# FOTA_Status_LED.net
KiCad netlist of a schematic drawn in Altium Designer
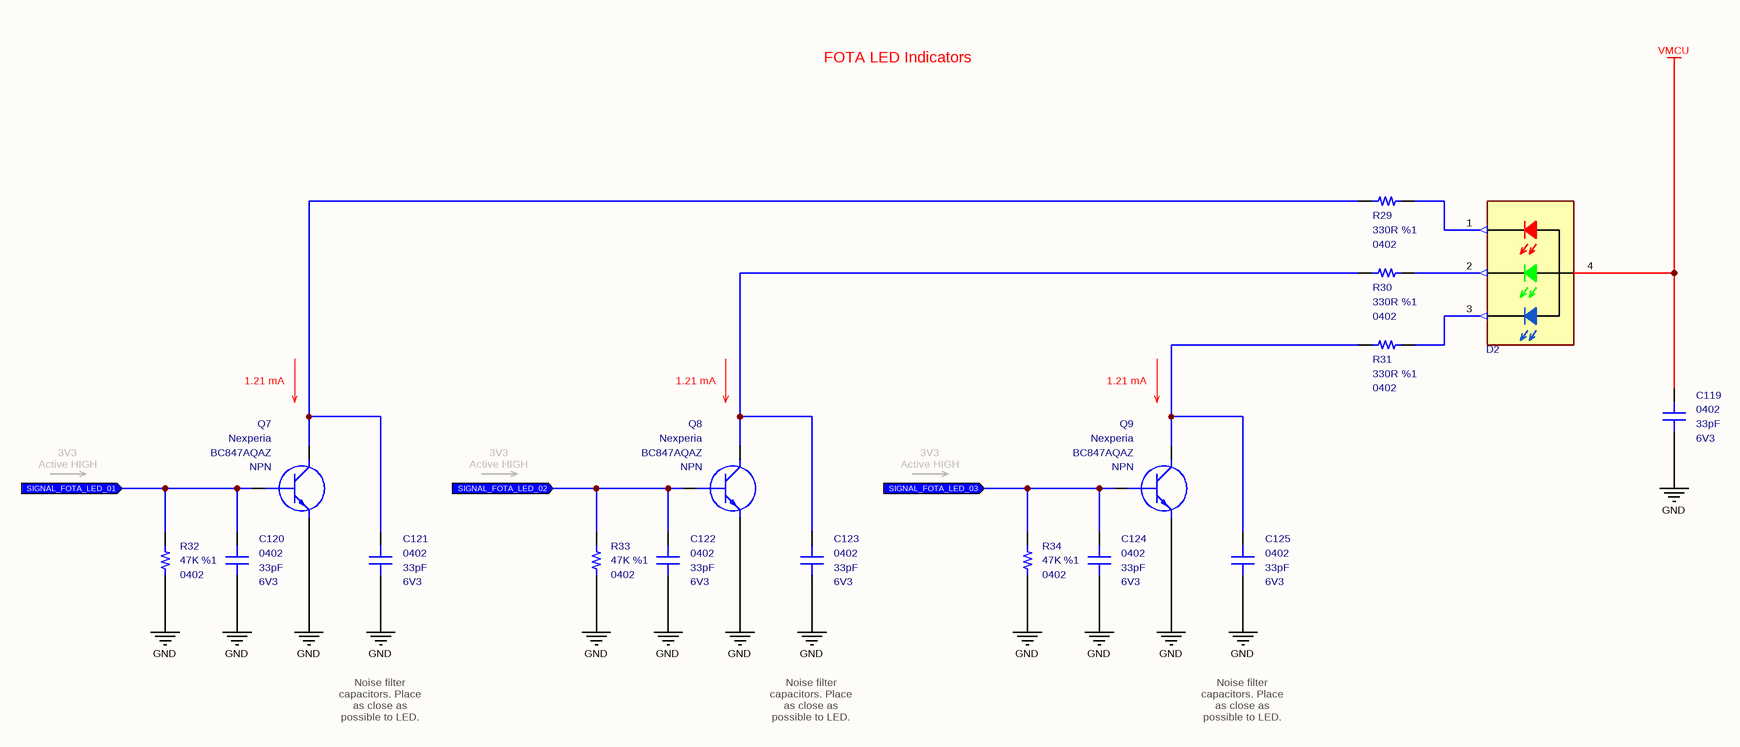
[diagram p0: FOTA Status LED.SchDoc]

(export (version "E")
  (design (tool "Eeschema 10.0.6"))
  (components
    (comp (ref "C119")
      (value "33pF")
      (footprint "CAPACITOR_0402")
      (description "Capacitor - 33pF [0402] (Ceramic)")
      (fields
        (field (name "MANUFACTURER_PART_NUMBER") "C0402C330J9RACAUTO")
        (field (name "MOUSER_PART_NUMBER") "80-C0402C330J9RAUTO")
        (field (name "CASE") "0402")
        (field (name "VOLTAGE") "6V3")
      )
      (libsource (lib "Ovoo_Schematic") (part "Capacitor - 33pF [0402-6V3]"))
    )
    (comp (ref "C120")
      (value "33pF")
      (footprint "CAPACITOR_0402")
      (description "Capacitor - 33pF [0402] (Ceramic)")
      (fields
        (field (name "MANUFACTURER_PART_NUMBER") "C0402C330J9RACAUTO")
        (field (name "MOUSER_PART_NUMBER") "80-C0402C330J9RAUTO")
        (field (name "CASE") "0402")
        (field (name "VOLTAGE") "6V3")
      )
      (libsource (lib "Ovoo_Schematic") (part "Capacitor - 33pF [0402-6V3]"))
    )
    (comp (ref "C121")
      (value "33pF")
      (footprint "CAPACITOR_0402")
      (description "Capacitor - 33pF [0402] (Ceramic)")
      (fields
        (field (name "MANUFACTURER_PART_NUMBER") "C0402C330J9RACAUTO")
        (field (name "MOUSER_PART_NUMBER") "80-C0402C330J9RAUTO")
        (field (name "CASE") "0402")
        (field (name "VOLTAGE") "6V3")
      )
      (libsource (lib "Ovoo_Schematic") (part "Capacitor - 33pF [0402-6V3]"))
    )
    (comp (ref "C122")
      (value "33pF")
      (footprint "CAPACITOR_0402")
      (description "Capacitor - 33pF [0402] (Ceramic)")
      (fields
        (field (name "MANUFACTURER_PART_NUMBER") "C0402C330J9RACAUTO")
        (field (name "MOUSER_PART_NUMBER") "80-C0402C330J9RAUTO")
        (field (name "CASE") "0402")
        (field (name "VOLTAGE") "6V3")
      )
      (libsource (lib "Ovoo_Schematic") (part "Capacitor - 33pF [0402-6V3]"))
    )
    (comp (ref "C123")
      (value "33pF")
      (footprint "CAPACITOR_0402")
      (description "Capacitor - 33pF [0402] (Ceramic)")
      (fields
        (field (name "MANUFACTURER_PART_NUMBER") "C0402C330J9RACAUTO")
        (field (name "MOUSER_PART_NUMBER") "80-C0402C330J9RAUTO")
        (field (name "CASE") "0402")
        (field (name "VOLTAGE") "6V3")
      )
      (libsource (lib "Ovoo_Schematic") (part "Capacitor - 33pF [0402-6V3]"))
    )
    (comp (ref "C124")
      (value "33pF")
      (footprint "CAPACITOR_0402")
      (description "Capacitor - 33pF [0402] (Ceramic)")
      (fields
        (field (name "MANUFACTURER_PART_NUMBER") "C0402C330J9RACAUTO")
        (field (name "MOUSER_PART_NUMBER") "80-C0402C330J9RAUTO")
        (field (name "CASE") "0402")
        (field (name "VOLTAGE") "6V3")
      )
      (libsource (lib "Ovoo_Schematic") (part "Capacitor - 33pF [0402-6V3]"))
    )
    (comp (ref "C125")
      (value "33pF")
      (footprint "CAPACITOR_0402")
      (description "Capacitor - 33pF [0402] (Ceramic)")
      (fields
        (field (name "MANUFACTURER_PART_NUMBER") "C0402C330J9RACAUTO")
        (field (name "MOUSER_PART_NUMBER") "80-C0402C330J9RAUTO")
        (field (name "CASE") "0402")
        (field (name "VOLTAGE") "6V3")
      )
      (libsource (lib "Ovoo_Schematic") (part "Capacitor - 33pF [0402-6V3]"))
    )
    (comp (ref "D2")
      (value "150066M153000")
      (footprint "Wurth_0606")
      (description "Standard LEDs - SMD PICOLED series Red LED")
      (fields (field (name "MOUSER PART NUMBER") "710-150066M153000"))
      (libsource (lib "Ovoo_Library") (part "Diode - RGB LED (150066M153000)"))
    )
    (comp (ref "Q7")
      (value "Bipolar NPN Transistors")
      (footprint "SOT1215")
      (description "Bipolar Transistors - BJT BC847AQA/DFN1010D-3/REEL 7\" Q2")
      (fields
        (field (name "MOUSER_PART_NUMBER") "771-BC847AQAZ")
        (field (name "MANUFACTURER_NAME") "Nexperia")
        (field (name "MANUFACTURER_PART_NUMBER") "BC847AQAZ")
        (field (name "POLARITY") "NPN")
      )
      (libsource (lib "Ovoo_Schematic") (part "Transistor - BC847"))
    )
    (comp (ref "Q8")
      (value "Bipolar NPN Transistors")
      (footprint "SOT1215")
      (description "Bipolar Transistors - BJT BC847AQA/DFN1010D-3/REEL 7\" Q2")
      (fields
        (field (name "MOUSER_PART_NUMBER") "771-BC847AQAZ")
        (field (name "MANUFACTURER_NAME") "Nexperia")
        (field (name "MANUFACTURER_PART_NUMBER") "BC847AQAZ")
        (field (name "POLARITY") "NPN")
      )
      (libsource (lib "Ovoo_Schematic") (part "Transistor - BC847"))
    )
    (comp (ref "Q9")
      (value "Bipolar NPN Transistors")
      (footprint "SOT1215")
      (description "Bipolar Transistors - BJT BC847AQA/DFN1010D-3/REEL 7\" Q2")
      (fields
        (field (name "MOUSER_PART_NUMBER") "771-BC847AQAZ")
        (field (name "MANUFACTURER_NAME") "Nexperia")
        (field (name "MANUFACTURER_PART_NUMBER") "BC847AQAZ")
        (field (name "POLARITY") "NPN")
      )
      (libsource (lib "Ovoo_Schematic") (part "Transistor - BC847"))
    )
    (comp (ref "R29")
      (value "330R")
      (footprint "RESISTOR_0402")
      (description "Thick Film Resistors - SMD 1/16 W 330 Ohm 1%")
      (fields
        (field (name "MANUFACTURER_PART_NUMBER") "CRCW0402330RFKED")
        (field (name "MOUSER_PART_NUMBER") "71-CRCW0402-330-E3")
        (field (name "TOLERANCE") "%1")
        (field (name "CASE") "0402")
      )
      (libsource (lib "Ovoo_Schematic") (part "Resistor - 330R"))
    )
    (comp (ref "R30")
      (value "330R")
      (footprint "RESISTOR_0402")
      (description "Thick Film Resistors - SMD 1/16 W 330 Ohm 1%")
      (fields
        (field (name "MANUFACTURER_PART_NUMBER") "CRCW0402330RFKED")
        (field (name "MOUSER_PART_NUMBER") "71-CRCW0402-330-E3")
        (field (name "TOLERANCE") "%1")
        (field (name "CASE") "0402")
      )
      (libsource (lib "Ovoo_Schematic") (part "Resistor - 330R"))
    )
    (comp (ref "R31")
      (value "330R")
      (footprint "RESISTOR_0402")
      (description "Thick Film Resistors - SMD 1/16 W 330 Ohm 1%")
      (fields
        (field (name "MANUFACTURER_PART_NUMBER") "CRCW0402330RFKED")
        (field (name "MOUSER_PART_NUMBER") "71-CRCW0402-330-E3")
        (field (name "TOLERANCE") "%1")
        (field (name "CASE") "0402")
      )
      (libsource (lib "Ovoo_Schematic") (part "Resistor - 330R"))
    )
    (comp (ref "R32")
      (value "47K")
      (footprint "RESISTOR_0402")
      (description "Thick Film Resistors - SMD 1/16 W 47 Kohms 1%")
      (fields
        (field (name "MANUFACTURER_PART_NUMBER") "CRCW040247K0FKED")
        (field (name "MOUSER_PART_NUMBER") "71-CRCW0402-47K-E3")
        (field (name "TOLERANCE") "%1")
        (field (name "CASE") "0402")
      )
      (libsource (lib "Ovoo_Schematic") (part "Resistor - 47K"))
    )
    (comp (ref "R33")
      (value "47K")
      (footprint "RESISTOR_0402")
      (description "Thick Film Resistors - SMD 1/16 W 47 Kohms 1%")
      (fields
        (field (name "MANUFACTURER_PART_NUMBER") "CRCW040247K0FKED")
        (field (name "MOUSER_PART_NUMBER") "71-CRCW0402-47K-E3")
        (field (name "TOLERANCE") "%1")
        (field (name "CASE") "0402")
      )
      (libsource (lib "Ovoo_Schematic") (part "Resistor - 47K"))
    )
    (comp (ref "R34")
      (value "47K")
      (footprint "RESISTOR_0402")
      (description "Thick Film Resistors - SMD 1/16 W 47 Kohms 1%")
      (fields
        (field (name "MANUFACTURER_PART_NUMBER") "CRCW040247K0FKED")
        (field (name "MOUSER_PART_NUMBER") "71-CRCW0402-47K-E3")
        (field (name "TOLERANCE") "%1")
        (field (name "CASE") "0402")
      )
      (libsource (lib "Ovoo_Schematic") (part "Resistor - 47K"))
    )
  )
  (nets
    (net (code "1") (name "/SIGNAL_FOTA_LED_01") (class "Default")
      (node (ref "C120") (pin "1") (pinfunction "1_1") (pintype "passive"))
      (node (ref "Q7") (pin "1") (pinfunction "B_1") (pintype "passive"))
      (node (ref "R32") (pin "2") (pinfunction "2_2") (pintype "passive"))
    )
    (net (code "2") (name "/SIGNAL_FOTA_LED_02") (class "Default")
      (node (ref "C122") (pin "1") (pinfunction "1_1") (pintype "passive"))
      (node (ref "Q8") (pin "1") (pinfunction "B_1") (pintype "passive"))
      (node (ref "R33") (pin "2") (pinfunction "2_2") (pintype "passive"))
    )
    (net (code "3") (name "/SIGNAL_FOTA_LED_03") (class "Default")
      (node (ref "C124") (pin "1") (pinfunction "1_1") (pintype "passive"))
      (node (ref "Q9") (pin "1") (pinfunction "B_1") (pintype "passive"))
      (node (ref "R34") (pin "2") (pinfunction "2_2") (pintype "passive"))
    )
    (net (code "4") (name "GND") (class "Default")
      (node (ref "C119") (pin "2") (pinfunction "2_2") (pintype "passive"))
      (node (ref "C120") (pin "2") (pinfunction "2_2") (pintype "passive"))
      (node (ref "C121") (pin "2") (pinfunction "2_2") (pintype "passive"))
      (node (ref "C122") (pin "2") (pinfunction "2_2") (pintype "passive"))
      (node (ref "C123") (pin "2") (pinfunction "2_2") (pintype "passive"))
      (node (ref "C124") (pin "2") (pinfunction "2_2") (pintype "passive"))
      (node (ref "C125") (pin "2") (pinfunction "2_2") (pintype "passive"))
      (node (ref "Q7") (pin "2") (pinfunction "E_2") (pintype "passive"))
      (node (ref "Q8") (pin "2") (pinfunction "E_2") (pintype "passive"))
      (node (ref "Q9") (pin "2") (pinfunction "E_2") (pintype "passive"))
      (node (ref "R32") (pin "1") (pinfunction "1_1") (pintype "passive"))
      (node (ref "R33") (pin "1") (pinfunction "1_1") (pintype "passive"))
      (node (ref "R34") (pin "1") (pinfunction "1_1") (pintype "passive"))
    )
    (net (code "5") (name "Net-(D2-Pad1)") (class "Default")
      (node (ref "D2") (pin "1") (pinfunction "1_1") (pintype "output"))
      (node (ref "R29") (pin "2") (pinfunction "2_2") (pintype "passive"))
    )
    (net (code "6") (name "Net-(D2-Pad2)") (class "Default")
      (node (ref "D2") (pin "2") (pinfunction "2_2") (pintype "output"))
      (node (ref "R30") (pin "2") (pinfunction "2_2") (pintype "passive"))
    )
    (net (code "7") (name "Net-(D2-Pad3)") (class "Default")
      (node (ref "D2") (pin "3") (pinfunction "3_3") (pintype "output"))
      (node (ref "R31") (pin "2") (pinfunction "2_2") (pintype "passive"))
    )
    (net (code "8") (name "Net-(Q7-C)") (class "Default")
      (node (ref "C121") (pin "1") (pinfunction "1_1") (pintype "passive"))
      (node (ref "Q7") (pin "3") (pinfunction "C_3") (pintype "passive"))
      (node (ref "R29") (pin "1") (pinfunction "1_1") (pintype "passive"))
    )
    (net (code "9") (name "Net-(Q8-C)") (class "Default")
      (node (ref "C123") (pin "1") (pinfunction "1_1") (pintype "passive"))
      (node (ref "Q8") (pin "3") (pinfunction "C_3") (pintype "passive"))
      (node (ref "R30") (pin "1") (pinfunction "1_1") (pintype "passive"))
    )
    (net (code "10") (name "Net-(Q9-C)") (class "Default")
      (node (ref "C125") (pin "1") (pinfunction "1_1") (pintype "passive"))
      (node (ref "Q9") (pin "3") (pinfunction "C_3") (pintype "passive"))
      (node (ref "R31") (pin "1") (pinfunction "1_1") (pintype "passive"))
    )
    (net (code "11") (name "VMCU") (class "Default")
      (node (ref "C119") (pin "1") (pinfunction "1_1") (pintype "passive"))
      (node (ref "D2") (pin "4") (pinfunction "4_4") (pintype "power_in"))
    )
  )
)
